# Main_Board_sub.net
KiCad netlist of a schematic drawn in EAGLE
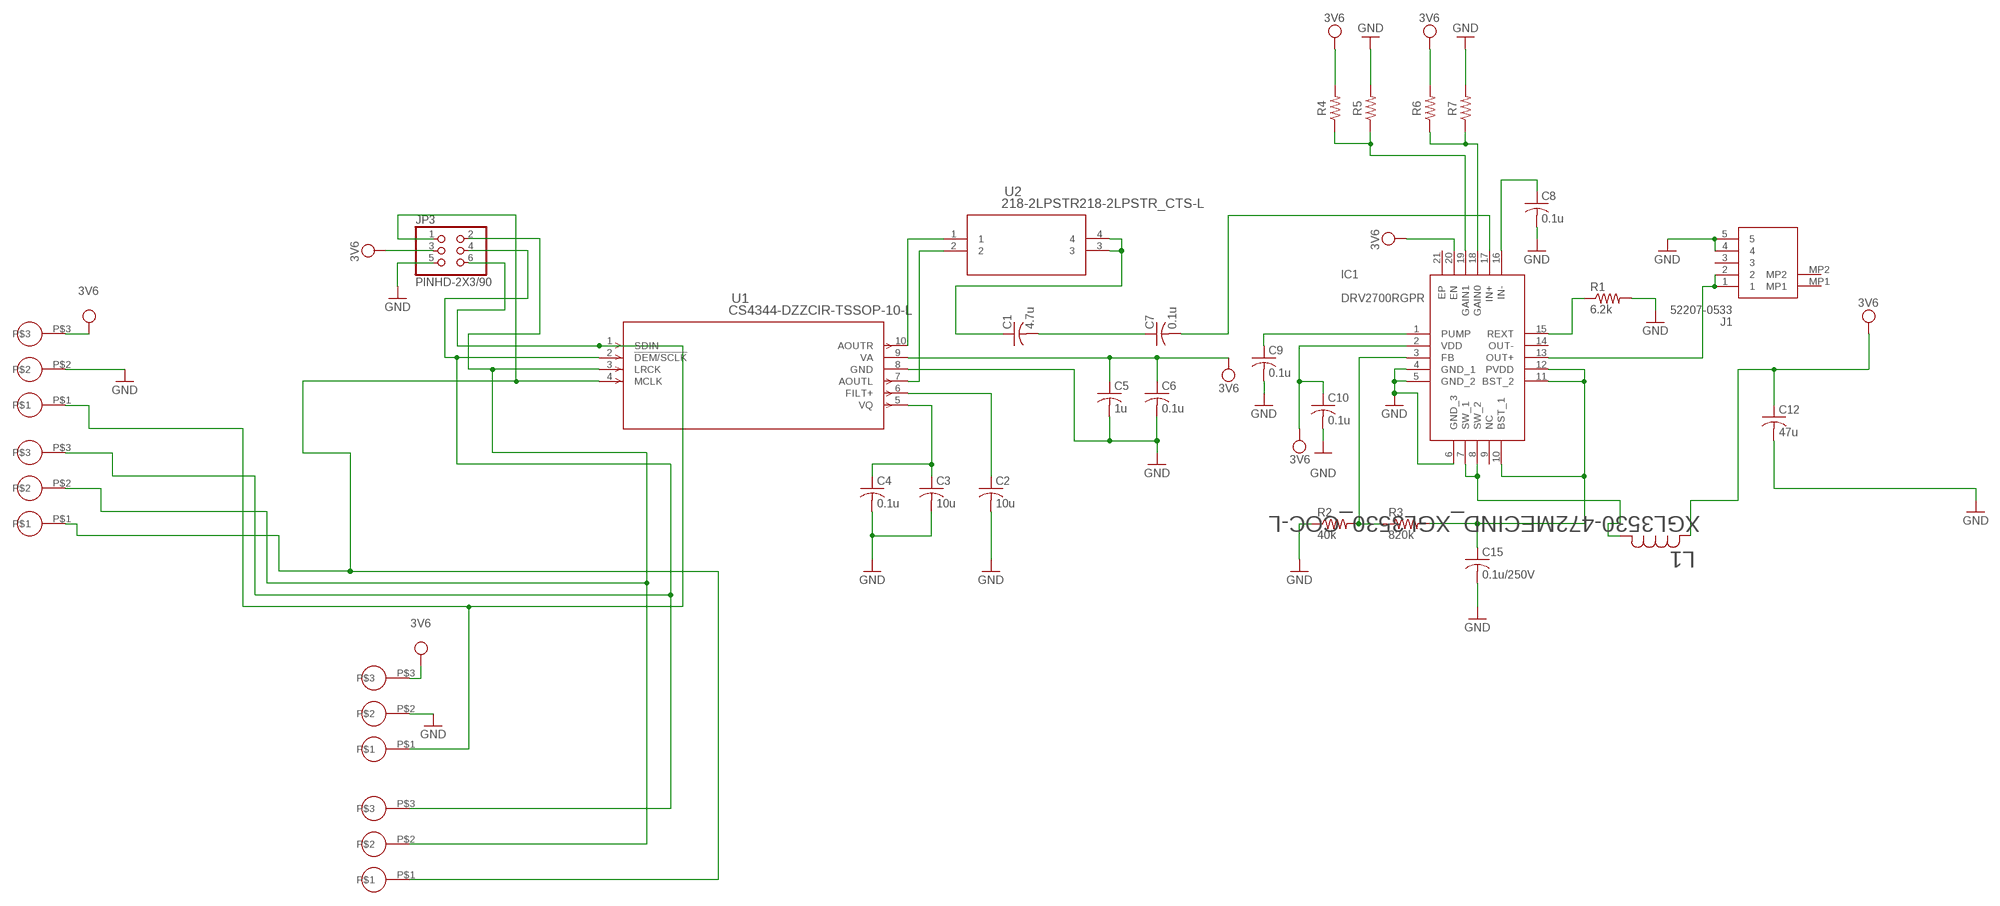
[diagram p0: schematic, sheet 1]

(export (version "E")
  (design (tool "Eeschema 10.0.6"))
  (components
    (comp (ref "C1")
      (value "4.7u")
      (footprint "eagle-import:CAPC1608X85")
      (libsource (lib "eagle-import") (part "C-USCHIP-0603(1608-METRIC)_"))
    )
    (comp (ref "C2")
      (value "10u")
      (footprint "eagle-import:CAPC1608X85")
      (libsource (lib "eagle-import") (part "C-USCHIP-0603(1608-METRIC)_"))
    )
    (comp (ref "C3")
      (value "10u")
      (footprint "eagle-import:CAPC1608X85")
      (libsource (lib "eagle-import") (part "C-USCHIP-0603(1608-METRIC)_"))
    )
    (comp (ref "C4")
      (value "0.1u")
      (footprint "eagle-import:CAPC1608X85")
      (libsource (lib "eagle-import") (part "C-USCHIP-0603(1608-METRIC)_"))
    )
    (comp (ref "C5")
      (value "1u")
      (footprint "eagle-import:CAPC1608X85")
      (libsource (lib "eagle-import") (part "C-USCHIP-0603(1608-METRIC)_"))
    )
    (comp (ref "C6")
      (value "0.1u")
      (footprint "eagle-import:CAPC1608X85")
      (libsource (lib "eagle-import") (part "C-USCHIP-0603(1608-METRIC)_"))
    )
    (comp (ref "C7")
      (value "0.1u")
      (footprint "eagle-import:CAPC1608X85")
      (libsource (lib "eagle-import") (part "C-USCHIP-0603(1608-METRIC)_"))
    )
    (comp (ref "C8")
      (value "0.1u")
      (footprint "eagle-import:CAPC1608X85")
      (libsource (lib "eagle-import") (part "C-USCHIP-0603(1608-METRIC)_"))
    )
    (comp (ref "C9")
      (value "0.1u")
      (footprint "eagle-import:CAPC1608X85")
      (libsource (lib "eagle-import") (part "C-USCHIP-0603(1608-METRIC)_"))
    )
    (comp (ref "C10")
      (value "0.1u")
      (footprint "eagle-import:CAPC1608X85")
      (libsource (lib "eagle-import") (part "C-USCHIP-0603(1608-METRIC)_"))
    )
    (comp (ref "C12")
      (value "47u")
      (footprint "eagle-import:CAPC1608X85")
      (libsource (lib "eagle-import") (part "C-USCHIP-0603(1608-METRIC)_"))
    )
    (comp (ref "C15")
      (value "0.1u/250V")
      (footprint "eagle-import:CAPC3216X135")
      (libsource (lib "eagle-import") (part "C-USCHIP-1206(3216-METRIC)_"))
    )
    (comp (ref "IC1")
      (value "DRV2700RGPR")
      (footprint "eagle-import:QFN50P400X400X100-21N")
      (fields (field (name "MOUSER_PART_NUMBER") "595-DRV2700RGPR"))
      (libsource (lib "eagle-import") (part "DRV2700RGPR"))
    )
    (comp (ref "J1")
      (value "52207-0533")
      (footprint "eagle-import:522070533")
      (fields (field (name "MOUSER_PART_NUMBER") "538-52207-0533"))
      (libsource (lib "eagle-import") (part "52207-0533"))
    )
    (comp (ref "JP3")
      (value "PINHD-2X3/90")
      (footprint "eagle-import:2X03_90")
      (fields (field (name "MANUFACTURER") "Generic"))
      (libsource (lib "eagle-import") (part "PINHD-2X3/90"))
    )
    (comp (ref "L1")
      (value "XGL3530-472MECIND_XGL3530_COC-L")
      (footprint "eagle-import:IND_XGL3530_COC-L")
      (fields
        (field (name "MANUFACTURER_PART_NUMBER") "XGL3530-472MEC")
        (field (name "COPYRIGHT") "Copyright (C) 2024 Ultra Librarian. All rights reserved.")
      )
      (libsource (lib "eagle-import") (part "XGL3530-472MECIND_XGL3530_COC-L"))
    )
    (comp (ref "R1")
      (value "6.2k")
      (footprint "eagle-import:RESC1608X60")
      (libsource (lib "eagle-import") (part "Tutorial - Fusion 360_16997205_R-USCHIP-0603(1608-METRIC)_"))
    )
    (comp (ref "R2")
      (value "40k")
      (footprint "eagle-import:RESC1608X60")
      (libsource (lib "eagle-import") (part "Tutorial - Fusion 360_16997205_R-USCHIP-0603(1608-METRIC)_"))
    )
    (comp (ref "R3")
      (value "820k")
      (footprint "eagle-import:RESC1608X60")
      (libsource (lib "eagle-import") (part "Tutorial - Fusion 360_16997205_R-USCHIP-0603(1608-METRIC)_"))
    )
    (comp (ref "R4")
      (value "R-US_CHIP-0603(1608-METRIC)")
      (footprint "eagle-import:RESC1608X60")
      (libsource (lib "eagle-import") (part "R-USCHIP-0603(1608-METRIC)_"))
    )
    (comp (ref "R5")
      (value "R-US_CHIP-0603(1608-METRIC)")
      (footprint "eagle-import:RESC1608X60")
      (libsource (lib "eagle-import") (part "R-USCHIP-0603(1608-METRIC)_"))
    )
    (comp (ref "R6")
      (value "R-US_CHIP-0603(1608-METRIC)")
      (footprint "eagle-import:RESC1608X60")
      (libsource (lib "eagle-import") (part "R-USCHIP-0603(1608-METRIC)_"))
    )
    (comp (ref "R7")
      (value "R-US_CHIP-0603(1608-METRIC)")
      (footprint "eagle-import:RESC1608X60")
      (libsource (lib "eagle-import") (part "R-USCHIP-0603(1608-METRIC)_"))
    )
    (comp (ref "U$1")
      (value "CONECTOR_MEM")
      (footprint "eagle-import:CONECTOR_MEM")
      (libsource (lib "eagle-import") (part "CONECTOR_MEM"))
    )
    (comp (ref "U$2")
      (value "CONECTOR_MEM")
      (footprint "eagle-import:CONECTOR_MEM")
      (libsource (lib "eagle-import") (part "CONECTOR_MEM"))
    )
    (comp (ref "U$3")
      (value "CONECTOR_MEM")
      (footprint "eagle-import:CONECTOR_MEM")
      (libsource (lib "eagle-import") (part "CONECTOR_MEM"))
    )
    (comp (ref "U$4")
      (value "CONECTOR_MEM")
      (footprint "eagle-import:CONECTOR_MEM")
      (libsource (lib "eagle-import") (part "CONECTOR_MEM"))
    )
    (comp (ref "U1")
      (value "CS4344-DZZCIR-TSSOP-10-L")
      (footprint "eagle-import:CIR-TSSOP-10-L")
      (fields
        (field (name "MANUFACTURER_PART_NUMBER") "CS4344-DZZ")
        (field (name "COPYRIGHT") "Copyright (C) 2024 Ultra Librarian. All rights reserved.")
      )
      (libsource (lib "eagle-import") (part "CS4344-DZZCIR-TSSOP-10-L"))
    )
    (comp (ref "U2")
      (value "218-2LPSTR218-2LPSTR_CTS-L")
      (footprint "eagle-import:218-2LPSTR_CTS-L")
      (fields
        (field (name "MANUFACTURER_PART_NUMBER") "218-2LPSTR")
        (field (name "COPYRIGHT") "Copyright (C) 2024 Ultra Librarian. All rights reserved.")
      )
      (libsource (lib "eagle-import") (part "218-2LPSTR218-2LPSTR_CTS-L"))
    )
  )
  (nets
    (net (code "1") (name "3V6") (class "Default")
      (node (ref "C10") (pin "1") (pinfunction "1_1") (pintype "passive"))
      (node (ref "C12") (pin "1") (pinfunction "1_1") (pintype "passive"))
      (node (ref "C5") (pin "1") (pinfunction "1_1") (pintype "passive"))
      (node (ref "C6") (pin "1") (pinfunction "1_1") (pintype "passive"))
      (node (ref "IC1") (pin "2") (pinfunction "VDD_2") (pintype "bidirectional"))
      (node (ref "IC1") (pin "20") (pinfunction "EN_20") (pintype "bidirectional"))
      (node (ref "JP3") (pin "3") (pinfunction "3_3") (pintype "passive"))
      (node (ref "L1") (pin "2") (pinfunction "2_2") (pintype "passive"))
      (node (ref "R4") (pin "2") (pinfunction "2_2") (pintype "passive"))
      (node (ref "R6") (pin "2") (pinfunction "2_2") (pintype "passive"))
      (node (ref "U$2") (pin "P$3") (pinfunction "P$3_P$3") (pintype "bidirectional"))
      (node (ref "U$3") (pin "P$3") (pinfunction "P$3_P$3") (pintype "bidirectional"))
      (node (ref "U1") (pin "9") (pinfunction "VA_9") (pintype "power_in"))
    )
    (net (code "2") (name "GND") (class "Default")
      (node (ref "C10") (pin "2") (pinfunction "2_2") (pintype "passive"))
      (node (ref "C12") (pin "2") (pinfunction "2_2") (pintype "passive"))
      (node (ref "C15") (pin "2") (pinfunction "2_2") (pintype "passive"))
      (node (ref "C2") (pin "2") (pinfunction "2_2") (pintype "passive"))
      (node (ref "C3") (pin "2") (pinfunction "2_2") (pintype "passive"))
      (node (ref "C4") (pin "2") (pinfunction "2_2") (pintype "passive"))
      (node (ref "C5") (pin "2") (pinfunction "2_2") (pintype "passive"))
      (node (ref "C6") (pin "2") (pinfunction "2_2") (pintype "passive"))
      (node (ref "C8") (pin "2") (pinfunction "2_2") (pintype "passive"))
      (node (ref "C9") (pin "2") (pinfunction "2_2") (pintype "passive"))
      (node (ref "IC1") (pin "4") (pinfunction "GND_1_4") (pintype "bidirectional"))
      (node (ref "IC1") (pin "5") (pinfunction "GND_2_5") (pintype "bidirectional"))
      (node (ref "IC1") (pin "6") (pinfunction "GND_3_6") (pintype "bidirectional"))
      (node (ref "J1") (pin "4") (pinfunction "4_4") (pintype "bidirectional"))
      (node (ref "J1") (pin "5") (pinfunction "5_5") (pintype "bidirectional"))
      (node (ref "JP3") (pin "5") (pinfunction "5_5") (pintype "passive"))
      (node (ref "R1") (pin "2") (pinfunction "2_2") (pintype "passive"))
      (node (ref "R2") (pin "1") (pinfunction "1_1") (pintype "passive"))
      (node (ref "R5") (pin "2") (pinfunction "2_2") (pintype "passive"))
      (node (ref "R7") (pin "2") (pinfunction "2_2") (pintype "passive"))
      (node (ref "U$2") (pin "P$2") (pinfunction "P$2_P$2") (pintype "bidirectional"))
      (node (ref "U$3") (pin "P$2") (pinfunction "P$2_P$2") (pintype "bidirectional"))
      (node (ref "U1") (pin "8") (pinfunction "GND_8") (pintype "power_in"))
    )
    (net (code "3") (name "Net-(C1-Pad1)") (class "Default")
      (node (ref "C1") (pin "1") (pinfunction "1_1") (pintype "passive"))
      (node (ref "U2") (pin "3") (pinfunction "3_3") (pintype "passive"))
      (node (ref "U2") (pin "4") (pinfunction "4_4") (pintype "passive"))
    )
    (net (code "4") (name "Net-(C1-Pad2)") (class "Default")
      (node (ref "C1") (pin "2") (pinfunction "2_2") (pintype "passive"))
      (node (ref "C7") (pin "1") (pinfunction "1_1") (pintype "passive"))
    )
    (net (code "5") (name "Net-(IC1-BST_1)") (class "Default")
      (node (ref "C15") (pin "1") (pinfunction "1_1") (pintype "passive"))
      (node (ref "IC1") (pin "10") (pinfunction "BST_1_10") (pintype "bidirectional"))
      (node (ref "IC1") (pin "11") (pinfunction "BST_2_11") (pintype "bidirectional"))
      (node (ref "IC1") (pin "12") (pinfunction "PVDD_12") (pintype "bidirectional"))
      (node (ref "R3") (pin "2") (pinfunction "2_2") (pintype "passive"))
    )
    (net (code "6") (name "Net-(IC1-FB)") (class "Default")
      (node (ref "IC1") (pin "3") (pinfunction "FB_3") (pintype "bidirectional"))
      (node (ref "R2") (pin "2") (pinfunction "2_2") (pintype "passive"))
      (node (ref "R3") (pin "1") (pinfunction "1_1") (pintype "passive"))
    )
    (net (code "7") (name "Net-(IC1-GAIN0)") (class "Default")
      (node (ref "IC1") (pin "18") (pinfunction "GAIN0_18") (pintype "bidirectional"))
      (node (ref "R6") (pin "1") (pinfunction "1_1") (pintype "passive"))
      (node (ref "R7") (pin "1") (pinfunction "1_1") (pintype "passive"))
    )
    (net (code "8") (name "Net-(IC1-GAIN1)") (class "Default")
      (node (ref "IC1") (pin "19") (pinfunction "GAIN1_19") (pintype "bidirectional"))
      (node (ref "R4") (pin "1") (pinfunction "1_1") (pintype "passive"))
      (node (ref "R5") (pin "1") (pinfunction "1_1") (pintype "passive"))
    )
    (net (code "9") (name "Net-(IC1-IN+)") (class "Default")
      (node (ref "C7") (pin "2") (pinfunction "2_2") (pintype "passive"))
      (node (ref "IC1") (pin "17") (pinfunction "IN+_17") (pintype "bidirectional"))
    )
    (net (code "10") (name "Net-(IC1-IN-)") (class "Default")
      (node (ref "C8") (pin "1") (pinfunction "1_1") (pintype "passive"))
      (node (ref "IC1") (pin "16") (pinfunction "IN-_16") (pintype "bidirectional"))
    )
    (net (code "11") (name "Net-(IC1-OUT+)") (class "Default")
      (node (ref "IC1") (pin "13") (pinfunction "OUT+_13") (pintype "bidirectional"))
      (node (ref "J1") (pin "1") (pinfunction "1_1") (pintype "bidirectional"))
      (node (ref "J1") (pin "2") (pinfunction "2_2") (pintype "bidirectional"))
    )
    (net (code "12") (name "Net-(IC1-PUMP)") (class "Default")
      (node (ref "C9") (pin "1") (pinfunction "1_1") (pintype "passive"))
      (node (ref "IC1") (pin "1") (pinfunction "PUMP_1") (pintype "bidirectional"))
    )
    (net (code "13") (name "Net-(IC1-REXT)") (class "Default")
      (node (ref "IC1") (pin "15") (pinfunction "REXT_15") (pintype "bidirectional"))
      (node (ref "R1") (pin "1") (pinfunction "1_1") (pintype "passive"))
    )
    (net (code "14") (name "Net-(IC1-SW_1)") (class "Default")
      (node (ref "IC1") (pin "7") (pinfunction "SW_1_7") (pintype "bidirectional"))
      (node (ref "IC1") (pin "8") (pinfunction "SW_2_8") (pintype "bidirectional"))
      (node (ref "L1") (pin "1") (pinfunction "1_1") (pintype "passive"))
    )
    (net (code "15") (name "Net-(U1-AOUTL)") (class "Default")
      (node (ref "U1") (pin "7") (pinfunction "AOUTL_7") (pintype "output"))
      (node (ref "U2") (pin "2") (pinfunction "2_2") (pintype "passive"))
    )
    (net (code "16") (name "Net-(U1-AOUTR)") (class "Default")
      (node (ref "U1") (pin "10") (pinfunction "AOUTR_10") (pintype "output"))
      (node (ref "U2") (pin "1") (pinfunction "1_1") (pintype "passive"))
    )
    (net (code "17") (name "Net-(U1-FILT+)") (class "Default")
      (node (ref "C2") (pin "1") (pinfunction "1_1") (pintype "passive"))
      (node (ref "U1") (pin "6") (pinfunction "FILT+_6") (pintype "output"))
    )
    (net (code "18") (name "Net-(U1-LRCK)") (class "Default")
      (node (ref "JP3") (pin "2") (pinfunction "2_2") (pintype "passive"))
      (node (ref "U$1") (pin "P$2") (pinfunction "P$2_P$2") (pintype "bidirectional"))
      (node (ref "U$4") (pin "P$2") (pinfunction "P$2_P$2") (pintype "bidirectional"))
      (node (ref "U1") (pin "3") (pinfunction "LRCK_3") (pintype "input"))
    )
    (net (code "19") (name "Net-(U1-MCLK)") (class "Default")
      (node (ref "JP3") (pin "1") (pinfunction "1_1") (pintype "passive"))
      (node (ref "U$1") (pin "P$1") (pinfunction "P$1_P$1") (pintype "bidirectional"))
      (node (ref "U$4") (pin "P$1") (pinfunction "P$1_P$1") (pintype "bidirectional"))
      (node (ref "U1") (pin "4") (pinfunction "MCLK_4") (pintype "input"))
    )
    (net (code "20") (name "Net-(U1-SDIN)") (class "Default")
      (node (ref "JP3") (pin "6") (pinfunction "6_6") (pintype "passive"))
      (node (ref "U$2") (pin "P$1") (pinfunction "P$1_P$1") (pintype "bidirectional"))
      (node (ref "U$3") (pin "P$1") (pinfunction "P$1_P$1") (pintype "bidirectional"))
      (node (ref "U1") (pin "1") (pinfunction "SDIN_1") (pintype "input"))
    )
    (net (code "21") (name "Net-(U1-VQ)") (class "Default")
      (node (ref "C3") (pin "1") (pinfunction "1_1") (pintype "passive"))
      (node (ref "C4") (pin "1") (pinfunction "1_1") (pintype "passive"))
      (node (ref "U1") (pin "5") (pinfunction "VQ_5") (pintype "output"))
    )
    (net (code "22") (name "Net-(U1-~{DEM{slash}SCLK})") (class "Default")
      (node (ref "JP3") (pin "4") (pinfunction "4_4") (pintype "passive"))
      (node (ref "U$1") (pin "P$3") (pinfunction "P$3_P$3") (pintype "bidirectional"))
      (node (ref "U$4") (pin "P$3") (pinfunction "P$3_P$3") (pintype "bidirectional"))
      (node (ref "U1") (pin "2") (pinfunction "~{DEM/SCLK}_2") (pintype "input"))
    )
    (net (code "23") (name "unconnected-(IC1-EP-Pad21)") (class "Default")
      (node (ref "IC1") (pin "21") (pinfunction "EP_21") (pintype "bidirectional"))
    )
    (net (code "24") (name "unconnected-(IC1-NC-Pad9)") (class "Default")
      (node (ref "IC1") (pin "9") (pinfunction "NC_9") (pintype "no_connect"))
    )
    (net (code "25") (name "unconnected-(IC1-OUT--Pad14)") (class "Default")
      (node (ref "IC1") (pin "14") (pinfunction "OUT-_14") (pintype "bidirectional"))
    )
    (net (code "26") (name "unconnected-(J1-Pad3)") (class "Default")
      (node (ref "J1") (pin "3") (pinfunction "3_3") (pintype "bidirectional"))
    )
    (net (code "27") (name "unconnected-(J1-PadMP1)") (class "Default")
      (node (ref "J1") (pin "MP1") (pinfunction "MP1_MP1") (pintype "bidirectional"))
    )
    (net (code "28") (name "unconnected-(J1-PadMP2)") (class "Default")
      (node (ref "J1") (pin "MP2") (pinfunction "MP2_MP2") (pintype "bidirectional"))
    )
  )
)
